# motor_driver_ver3_8.net
KiCad netlist of a schematic drawn in EAGLE
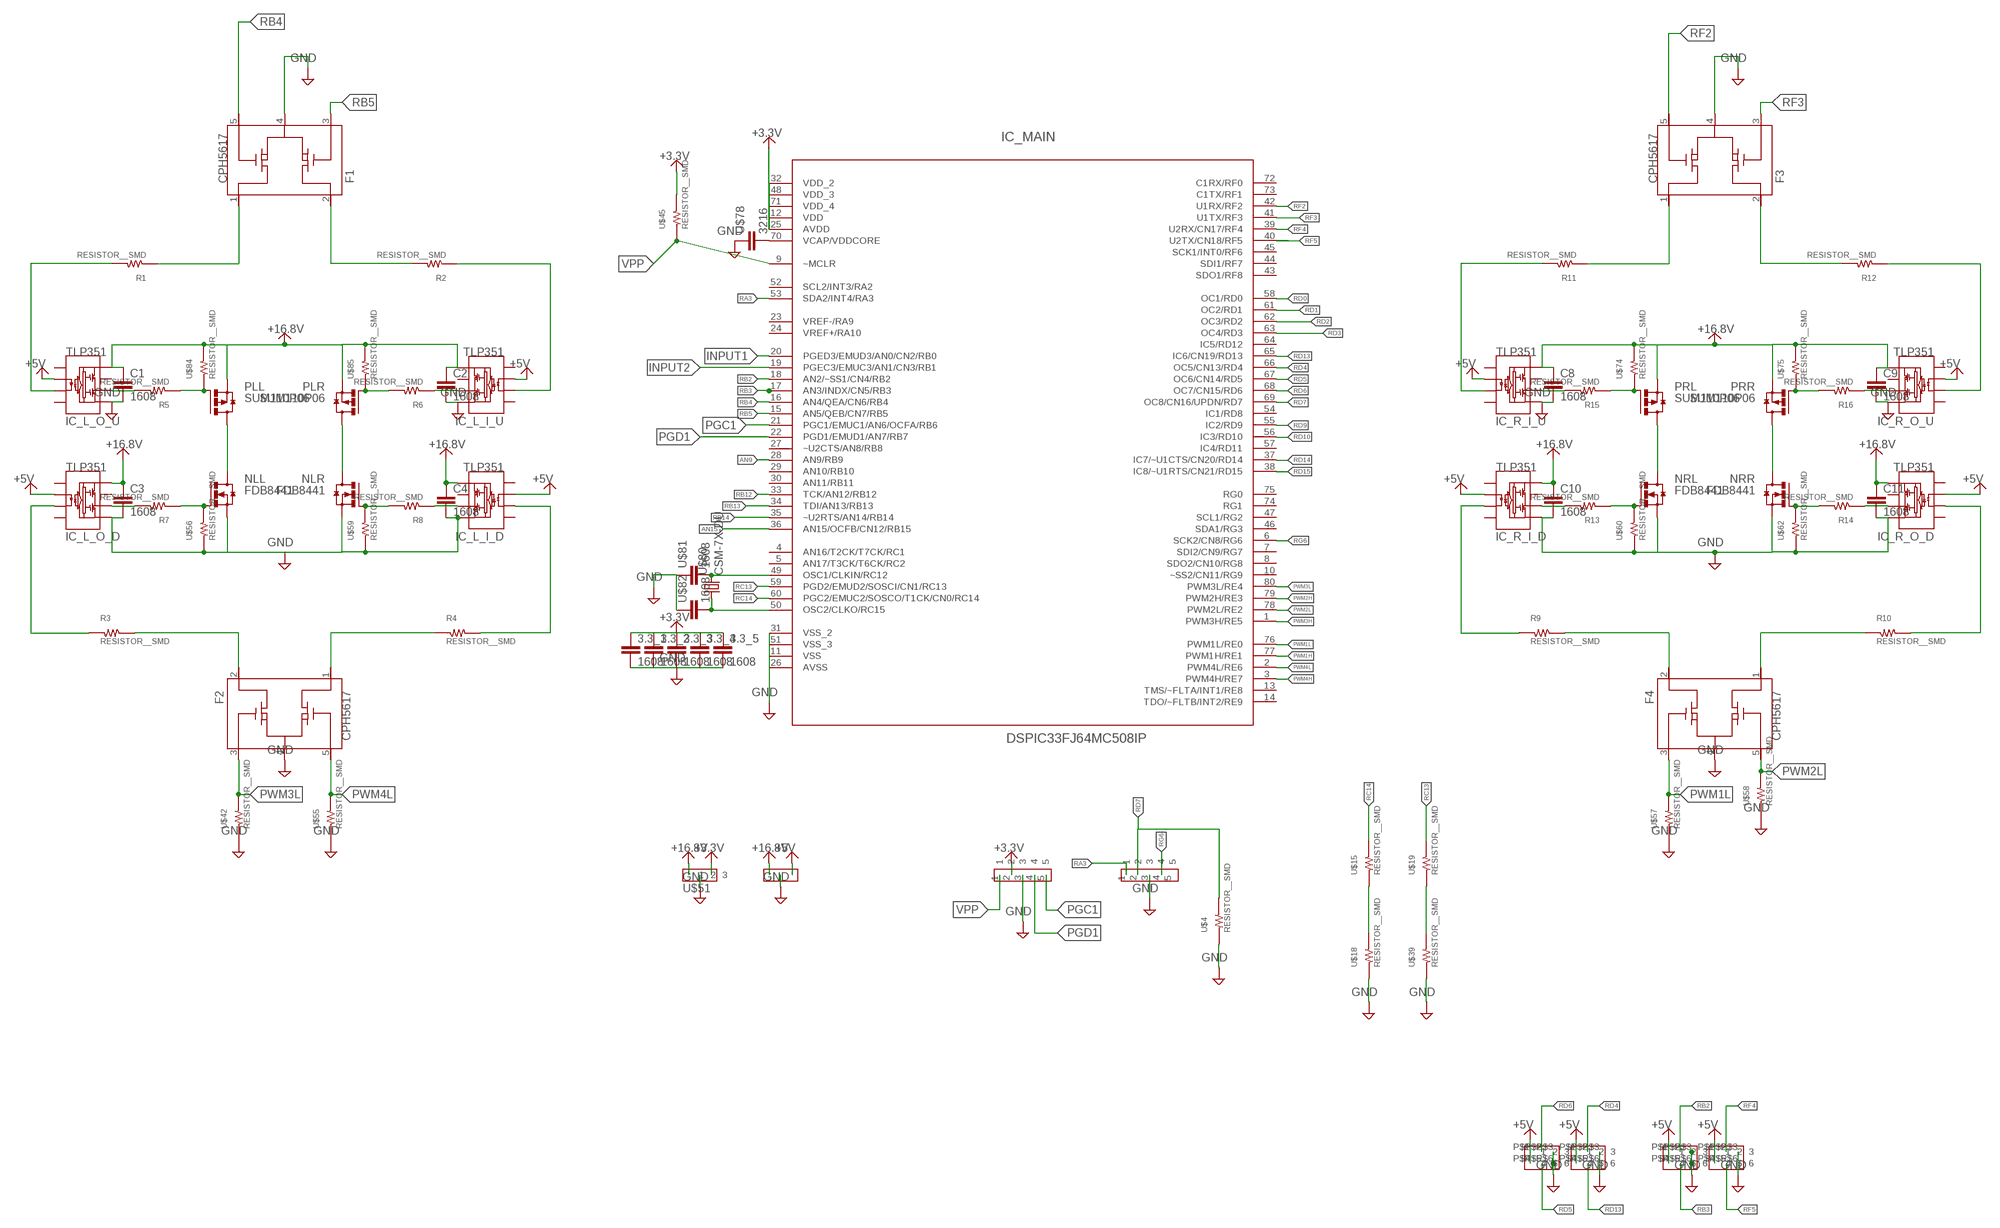
[diagram p0: schematic, sheet 1]

(export (version "E")
  (design (tool "Eeschema 10.0.6"))
  (components
    (comp (ref "3.3_1")
      (value "1608")
      (footprint "eagle-import:1608")
      (libsource (lib "eagle-import") (part "1608"))
    )
    (comp (ref "3.3_2")
      (value "1608")
      (footprint "eagle-import:1608")
      (libsource (lib "eagle-import") (part "1608"))
    )
    (comp (ref "3.3_3")
      (value "1608")
      (footprint "eagle-import:1608")
      (libsource (lib "eagle-import") (part "1608"))
    )
    (comp (ref "3.3_4")
      (value "1608")
      (footprint "eagle-import:1608")
      (libsource (lib "eagle-import") (part "1608"))
    )
    (comp (ref "3.3_5")
      (value "1608")
      (footprint "eagle-import:1608")
      (libsource (lib "eagle-import") (part "1608"))
    )
    (comp (ref "C1")
      (value "1608")
      (footprint "eagle-import:1608")
      (libsource (lib "eagle-import") (part "1608"))
    )
    (comp (ref "C2")
      (value "1608")
      (footprint "eagle-import:1608")
      (libsource (lib "eagle-import") (part "1608"))
    )
    (comp (ref "C3")
      (value "1608")
      (footprint "eagle-import:1608")
      (libsource (lib "eagle-import") (part "1608"))
    )
    (comp (ref "C4")
      (value "1608")
      (footprint "eagle-import:1608")
      (libsource (lib "eagle-import") (part "1608"))
    )
    (comp (ref "C8")
      (value "1608")
      (footprint "eagle-import:1608")
      (libsource (lib "eagle-import") (part "1608"))
    )
    (comp (ref "C9")
      (value "1608")
      (footprint "eagle-import:1608")
      (libsource (lib "eagle-import") (part "1608"))
    )
    (comp (ref "C10")
      (value "1608")
      (footprint "eagle-import:1608")
      (libsource (lib "eagle-import") (part "1608"))
    )
    (comp (ref "C11")
      (value "1608")
      (footprint "eagle-import:1608")
      (libsource (lib "eagle-import") (part "1608"))
    )
    (comp (ref "F1")
      (value "CPH5617")
      (footprint "eagle-import:CHP-5")
      (libsource (lib "eagle-import") (part "CPH5617"))
    )
    (comp (ref "F2")
      (value "CPH5617")
      (footprint "eagle-import:CHP-5")
      (libsource (lib "eagle-import") (part "CPH5617"))
    )
    (comp (ref "F3")
      (value "CPH5617")
      (footprint "eagle-import:CHP-5")
      (libsource (lib "eagle-import") (part "CPH5617"))
    )
    (comp (ref "F4")
      (value "CPH5617")
      (footprint "eagle-import:CHP-5")
      (libsource (lib "eagle-import") (part "CPH5617"))
    )
    (comp (ref "IC_L_I_D")
      (value "TLP351")
      (footprint "eagle-import:DIL08")
      (libsource (lib "eagle-import") (part "TLP351"))
    )
    (comp (ref "IC_L_I_U")
      (value "TLP351")
      (footprint "eagle-import:DIL08")
      (libsource (lib "eagle-import") (part "TLP351"))
    )
    (comp (ref "IC_L_O_D")
      (value "TLP351")
      (footprint "eagle-import:DIL08")
      (libsource (lib "eagle-import") (part "TLP351"))
    )
    (comp (ref "IC_L_O_U")
      (value "TLP351")
      (footprint "eagle-import:DIL08")
      (libsource (lib "eagle-import") (part "TLP351"))
    )
    (comp (ref "IC_MAIN")
      (value "DSPIC33FJ64MC508IP")
      (footprint "eagle-import:QFP50P1400X1400X120-80N")
      (libsource (lib "eagle-import") (part "DSPIC33FJ64MC508IP"))
    )
    (comp (ref "IC_R_I_D")
      (value "TLP351")
      (footprint "eagle-import:DIL08")
      (libsource (lib "eagle-import") (part "TLP351"))
    )
    (comp (ref "IC_R_I_U")
      (value "TLP351")
      (footprint "eagle-import:DIL08")
      (libsource (lib "eagle-import") (part "TLP351"))
    )
    (comp (ref "IC_R_O_D")
      (value "TLP351")
      (footprint "eagle-import:DIL08")
      (libsource (lib "eagle-import") (part "TLP351"))
    )
    (comp (ref "IC_R_O_U")
      (value "TLP351")
      (footprint "eagle-import:DIL08")
      (libsource (lib "eagle-import") (part "TLP351"))
    )
    (comp (ref "NLL")
      (value "FDB8441")
      (footprint "eagle-import:TO-263")
      (libsource (lib "eagle-import") (part "FDB8441"))
    )
    (comp (ref "NLR")
      (value "FDB8441")
      (footprint "eagle-import:TO-263")
      (libsource (lib "eagle-import") (part "FDB8441"))
    )
    (comp (ref "NRL")
      (value "FDB8441")
      (footprint "eagle-import:TO-263")
      (libsource (lib "eagle-import") (part "FDB8441"))
    )
    (comp (ref "NRR")
      (value "FDB8441")
      (footprint "eagle-import:TO-263")
      (libsource (lib "eagle-import") (part "FDB8441"))
    )
    (comp (ref "PLL")
      (value "SUM110P06")
      (footprint "eagle-import:TO-263")
      (libsource (lib "eagle-import") (part "SUM110P06"))
    )
    (comp (ref "PLR")
      (value "SUM110P06")
      (footprint "eagle-import:TO-263")
      (libsource (lib "eagle-import") (part "SUM110P06"))
    )
    (comp (ref "PRL")
      (value "SUM110P06")
      (footprint "eagle-import:TO-263")
      (libsource (lib "eagle-import") (part "SUM110P06"))
    )
    (comp (ref "PRR")
      (value "SUM110P06")
      (footprint "eagle-import:TO-263")
      (libsource (lib "eagle-import") (part "SUM110P06"))
    )
    (comp (ref "R1")
      (value "RESISTOR__SMD")
      (footprint "eagle-import:1608")
      (libsource (lib "eagle-import") (part "RESISTOR__SMD"))
    )
    (comp (ref "R2")
      (value "RESISTOR__SMD")
      (footprint "eagle-import:1608")
      (libsource (lib "eagle-import") (part "RESISTOR__SMD"))
    )
    (comp (ref "R3")
      (value "RESISTOR__SMD")
      (footprint "eagle-import:1608")
      (libsource (lib "eagle-import") (part "RESISTOR__SMD"))
    )
    (comp (ref "R4")
      (value "RESISTOR__SMD")
      (footprint "eagle-import:1608")
      (libsource (lib "eagle-import") (part "RESISTOR__SMD"))
    )
    (comp (ref "R5")
      (value "RESISTOR__SMD")
      (footprint "eagle-import:1608")
      (libsource (lib "eagle-import") (part "RESISTOR__SMD"))
    )
    (comp (ref "R6")
      (value "RESISTOR__SMD")
      (footprint "eagle-import:1608")
      (libsource (lib "eagle-import") (part "RESISTOR__SMD"))
    )
    (comp (ref "R7")
      (value "RESISTOR__SMD")
      (footprint "eagle-import:1608")
      (libsource (lib "eagle-import") (part "RESISTOR__SMD"))
    )
    (comp (ref "R8")
      (value "RESISTOR__SMD")
      (footprint "eagle-import:1608")
      (libsource (lib "eagle-import") (part "RESISTOR__SMD"))
    )
    (comp (ref "R9")
      (value "RESISTOR__SMD")
      (footprint "eagle-import:1608")
      (libsource (lib "eagle-import") (part "RESISTOR__SMD"))
    )
    (comp (ref "R10")
      (value "RESISTOR__SMD")
      (footprint "eagle-import:1608")
      (libsource (lib "eagle-import") (part "RESISTOR__SMD"))
    )
    (comp (ref "R11")
      (value "RESISTOR__SMD")
      (footprint "eagle-import:1608")
      (libsource (lib "eagle-import") (part "RESISTOR__SMD"))
    )
    (comp (ref "R12")
      (value "RESISTOR__SMD")
      (footprint "eagle-import:1608")
      (libsource (lib "eagle-import") (part "RESISTOR__SMD"))
    )
    (comp (ref "R13")
      (value "RESISTOR__SMD")
      (footprint "eagle-import:1608")
      (libsource (lib "eagle-import") (part "RESISTOR__SMD"))
    )
    (comp (ref "R14")
      (value "RESISTOR__SMD")
      (footprint "eagle-import:1608")
      (libsource (lib "eagle-import") (part "RESISTOR__SMD"))
    )
    (comp (ref "R15")
      (value "RESISTOR__SMD")
      (footprint "eagle-import:1608")
      (libsource (lib "eagle-import") (part "RESISTOR__SMD"))
    )
    (comp (ref "R16")
      (value "RESISTOR__SMD")
      (footprint "eagle-import:1608")
      (libsource (lib "eagle-import") (part "RESISTOR__SMD"))
    )
    (comp (ref "U$1")
      (value "PIN_HEADER_5")
      (footprint "eagle-import:PIN_HEADER_5")
      (libsource (lib "eagle-import") (part "PIN_HEADER_5"))
    )
    (comp (ref "U$4")
      (value "RESISTOR__SMD")
      (footprint "eagle-import:1608")
      (libsource (lib "eagle-import") (part "RESISTOR__SMD"))
    )
    (comp (ref "U$5")
      (value "PIN_HEADER_32")
      (footprint "eagle-import:PIN_HEADER_3_2")
      (libsource (lib "eagle-import") (part "PIN_HEADER_32"))
    )
    (comp (ref "U$15")
      (value "RESISTOR__SMD")
      (footprint "eagle-import:1608")
      (libsource (lib "eagle-import") (part "RESISTOR__SMD"))
    )
    (comp (ref "U$18")
      (value "RESISTOR__SMD")
      (footprint "eagle-import:1608")
      (libsource (lib "eagle-import") (part "RESISTOR__SMD"))
    )
    (comp (ref "U$19")
      (value "RESISTOR__SMD")
      (footprint "eagle-import:1608")
      (libsource (lib "eagle-import") (part "RESISTOR__SMD"))
    )
    (comp (ref "U$20")
      (value "PIN_HEADER_32")
      (footprint "eagle-import:PIN_HEADER_3_2")
      (libsource (lib "eagle-import") (part "PIN_HEADER_32"))
    )
    (comp (ref "U$39")
      (value "RESISTOR__SMD")
      (footprint "eagle-import:1608")
      (libsource (lib "eagle-import") (part "RESISTOR__SMD"))
    )
    (comp (ref "U$42")
      (value "RESISTOR__SMD")
      (footprint "eagle-import:1608")
      (libsource (lib "eagle-import") (part "RESISTOR__SMD"))
    )
    (comp (ref "U$45")
      (value "RESISTOR__SMD")
      (footprint "eagle-import:1608")
      (libsource (lib "eagle-import") (part "RESISTOR__SMD"))
    )
    (comp (ref "U$47")
      (value "TA48M05")
      (footprint "eagle-import:ＨＳＩＰ３")
      (libsource (lib "eagle-import") (part "TA48M05"))
    )
    (comp (ref "U$51")
      (value "TA48M033")
      (footprint "eagle-import:ＨＳＩＰ３")
      (libsource (lib "eagle-import") (part "TA48M033"))
    )
    (comp (ref "U$55")
      (value "RESISTOR__SMD")
      (footprint "eagle-import:1608")
      (libsource (lib "eagle-import") (part "RESISTOR__SMD"))
    )
    (comp (ref "U$56")
      (value "RESISTOR__SMD")
      (footprint "eagle-import:1608")
      (libsource (lib "eagle-import") (part "RESISTOR__SMD"))
    )
    (comp (ref "U$57")
      (value "RESISTOR__SMD")
      (footprint "eagle-import:1608")
      (libsource (lib "eagle-import") (part "RESISTOR__SMD"))
    )
    (comp (ref "U$58")
      (value "RESISTOR__SMD")
      (footprint "eagle-import:1608")
      (libsource (lib "eagle-import") (part "RESISTOR__SMD"))
    )
    (comp (ref "U$59")
      (value "RESISTOR__SMD")
      (footprint "eagle-import:1608")
      (libsource (lib "eagle-import") (part "RESISTOR__SMD"))
    )
    (comp (ref "U$60")
      (value "RESISTOR__SMD")
      (footprint "eagle-import:1608")
      (libsource (lib "eagle-import") (part "RESISTOR__SMD"))
    )
    (comp (ref "U$62")
      (value "RESISTOR__SMD")
      (footprint "eagle-import:1608")
      (libsource (lib "eagle-import") (part "RESISTOR__SMD"))
    )
    (comp (ref "U$64")
      (value "PIN_HEADER_5")
      (footprint "eagle-import:PIN_HEADER_5")
      (libsource (lib "eagle-import") (part "PIN_HEADER_5"))
    )
    (comp (ref "U$66")
      (value "PIN_HEADER_32")
      (footprint "eagle-import:PIN_HEADER_3_2")
      (libsource (lib "eagle-import") (part "PIN_HEADER_32"))
    )
    (comp (ref "U$67")
      (value "PIN_HEADER_32")
      (footprint "eagle-import:PIN_HEADER_3_2")
      (libsource (lib "eagle-import") (part "PIN_HEADER_32"))
    )
    (comp (ref "U$74")
      (value "RESISTOR__SMD")
      (footprint "eagle-import:1608")
      (libsource (lib "eagle-import") (part "RESISTOR__SMD"))
    )
    (comp (ref "U$75")
      (value "RESISTOR__SMD")
      (footprint "eagle-import:1608")
      (libsource (lib "eagle-import") (part "RESISTOR__SMD"))
    )
    (comp (ref "U$78")
      (value "3216")
      (footprint "eagle-import:3216")
      (libsource (lib "eagle-import") (part "3216"))
    )
    (comp (ref "U$80")
      (value "CSM-7X-DU")
      (footprint "eagle-import:CSM-7X-DU")
      (libsource (lib "eagle-import") (part "CSM-7X-DU"))
    )
    (comp (ref "U$81")
      (value "1608")
      (footprint "eagle-import:1608")
      (libsource (lib "eagle-import") (part "1608"))
    )
    (comp (ref "U$82")
      (value "1608")
      (footprint "eagle-import:1608")
      (libsource (lib "eagle-import") (part "1608"))
    )
    (comp (ref "U$84")
      (value "RESISTOR__SMD")
      (footprint "eagle-import:1608")
      (libsource (lib "eagle-import") (part "RESISTOR__SMD"))
    )
    (comp (ref "U$85")
      (value "RESISTOR__SMD")
      (footprint "eagle-import:1608")
      (libsource (lib "eagle-import") (part "RESISTOR__SMD"))
    )
  )
  (nets
    (net (code "1") (name "+3.3V") (class "Default")
      (node (ref "3.3_1") (pin "P$1") (pinfunction "1_P$1") (pintype "passive"))
      (node (ref "3.3_2") (pin "P$1") (pinfunction "1_P$1") (pintype "passive"))
      (node (ref "3.3_3") (pin "P$1") (pinfunction "1_P$1") (pintype "passive"))
      (node (ref "3.3_4") (pin "P$1") (pinfunction "1_P$1") (pintype "passive"))
      (node (ref "3.3_5") (pin "P$1") (pinfunction "1_P$1") (pintype "passive"))
      (node (ref "IC_MAIN") (pin "12") (pinfunction "VDD_12") (pintype "power_in"))
      (node (ref "IC_MAIN") (pin "25") (pinfunction "AVDD_25") (pintype "power_in"))
      (node (ref "IC_MAIN") (pin "32") (pinfunction "VDD_2_32") (pintype "power_in"))
      (node (ref "IC_MAIN") (pin "48") (pinfunction "VDD_3_48") (pintype "power_in"))
      (node (ref "IC_MAIN") (pin "71") (pinfunction "VDD_4_71") (pintype "power_in"))
      (node (ref "U$1") (pin "2") (pinfunction "2_2") (pintype "bidirectional"))
      (node (ref "U$45") (pin "2") (pinfunction "P$2_2") (pintype "passive"))
      (node (ref "U$51") (pin "3") (pinfunction "3_3") (pintype "bidirectional"))
    )
    (net (code "2") (name "+5V") (class "Default")
      (node (ref "IC_L_I_D") (pin "2") (pinfunction "LED+_2") (pintype "bidirectional"))
      (node (ref "IC_L_I_U") (pin "2") (pinfunction "LED+_2") (pintype "bidirectional"))
      (node (ref "IC_L_O_D") (pin "2") (pinfunction "LED+_2") (pintype "bidirectional"))
      (node (ref "IC_L_O_U") (pin "2") (pinfunction "LED+_2") (pintype "bidirectional"))
      (node (ref "IC_R_I_D") (pin "2") (pinfunction "LED+_2") (pintype "bidirectional"))
      (node (ref "IC_R_I_U") (pin "2") (pinfunction "LED+_2") (pintype "bidirectional"))
      (node (ref "IC_R_O_D") (pin "2") (pinfunction "LED+_2") (pintype "bidirectional"))
      (node (ref "IC_R_O_U") (pin "2") (pinfunction "LED+_2") (pintype "bidirectional"))
      (node (ref "U$20") (pin "P$1") (pinfunction "1_P$1") (pintype "bidirectional"))
      (node (ref "U$20") (pin "P$4") (pinfunction "4_P$4") (pintype "bidirectional"))
      (node (ref "U$47") (pin "3") (pinfunction "OUT_3") (pintype "bidirectional"))
      (node (ref "U$5") (pin "P$1") (pinfunction "1_P$1") (pintype "bidirectional"))
      (node (ref "U$5") (pin "P$4") (pinfunction "4_P$4") (pintype "bidirectional"))
      (node (ref "U$66") (pin "P$1") (pinfunction "1_P$1") (pintype "bidirectional"))
      (node (ref "U$66") (pin "P$4") (pinfunction "4_P$4") (pintype "bidirectional"))
      (node (ref "U$67") (pin "P$1") (pinfunction "1_P$1") (pintype "bidirectional"))
      (node (ref "U$67") (pin "P$4") (pinfunction "4_P$4") (pintype "bidirectional"))
    )
    (net (code "3") (name "+16.8V") (class "Default")
      (node (ref "C1") (pin "P$1") (pinfunction "1_P$1") (pintype "passive"))
      (node (ref "C10") (pin "P$1") (pinfunction "1_P$1") (pintype "passive"))
      (node (ref "C11") (pin "P$1") (pinfunction "1_P$1") (pintype "passive"))
      (node (ref "C2") (pin "P$1") (pinfunction "1_P$1") (pintype "passive"))
      (node (ref "C3") (pin "P$1") (pinfunction "1_P$1") (pintype "passive"))
      (node (ref "C4") (pin "P$1") (pinfunction "1_P$1") (pintype "passive"))
      (node (ref "C8") (pin "P$1") (pinfunction "1_P$1") (pintype "passive"))
      (node (ref "C9") (pin "P$1") (pinfunction "1_P$1") (pintype "passive"))
      (node (ref "IC_L_I_D") (pin "8") (pinfunction "VDD_8") (pintype "bidirectional"))
      (node (ref "IC_L_I_U") (pin "8") (pinfunction "VDD_8") (pintype "bidirectional"))
      (node (ref "IC_L_O_D") (pin "8") (pinfunction "VDD_8") (pintype "bidirectional"))
      (node (ref "IC_L_O_U") (pin "8") (pinfunction "VDD_8") (pintype "bidirectional"))
      (node (ref "IC_R_I_D") (pin "8") (pinfunction "VDD_8") (pintype "bidirectional"))
      (node (ref "IC_R_I_U") (pin "8") (pinfunction "VDD_8") (pintype "bidirectional"))
      (node (ref "IC_R_O_D") (pin "8") (pinfunction "VDD_8") (pintype "bidirectional"))
      (node (ref "IC_R_O_U") (pin "8") (pinfunction "VDD_8") (pintype "bidirectional"))
      (node (ref "PLL") (pin "2") (pinfunction "S_2") (pintype "passive"))
      (node (ref "PLR") (pin "2") (pinfunction "S_2") (pintype "passive"))
      (node (ref "PRL") (pin "2") (pinfunction "S_2") (pintype "passive"))
      (node (ref "PRR") (pin "2") (pinfunction "S_2") (pintype "passive"))
      (node (ref "U$47") (pin "1") (pinfunction "IN_1") (pintype "bidirectional"))
      (node (ref "U$51") (pin "1") (pinfunction "1_1") (pintype "bidirectional"))
      (node (ref "U$74") (pin "2") (pinfunction "P$2_2") (pintype "passive"))
      (node (ref "U$75") (pin "2") (pinfunction "P$2_2") (pintype "passive"))
      (node (ref "U$84") (pin "2") (pinfunction "P$2_2") (pintype "passive"))
      (node (ref "U$85") (pin "2") (pinfunction "P$2_2") (pintype "passive"))
    )
    (net (code "4") (name "AN9") (class "Default")
      (node (ref "IC_MAIN") (pin "28") (pinfunction "AN9/RB9_28") (pintype "bidirectional"))
    )
    (net (code "5") (name "AN15") (class "Default")
      (node (ref "IC_MAIN") (pin "36") (pinfunction "AN15/OCFB/CN12/RB15_36") (pintype "bidirectional"))
    )
    (net (code "6") (name "GND") (class "Default")
      (node (ref "3.3_1") (pin "P$2") (pinfunction "2_P$2") (pintype "passive"))
      (node (ref "3.3_2") (pin "P$2") (pinfunction "2_P$2") (pintype "passive"))
      (node (ref "3.3_3") (pin "P$2") (pinfunction "2_P$2") (pintype "passive"))
      (node (ref "3.3_4") (pin "P$2") (pinfunction "2_P$2") (pintype "passive"))
      (node (ref "3.3_5") (pin "P$2") (pinfunction "2_P$2") (pintype "passive"))
      (node (ref "C1") (pin "P$2") (pinfunction "2_P$2") (pintype "passive"))
      (node (ref "C10") (pin "P$2") (pinfunction "2_P$2") (pintype "passive"))
      (node (ref "C11") (pin "P$2") (pinfunction "2_P$2") (pintype "passive"))
      (node (ref "C2") (pin "P$2") (pinfunction "2_P$2") (pintype "passive"))
      (node (ref "C3") (pin "P$2") (pinfunction "2_P$2") (pintype "passive"))
      (node (ref "C4") (pin "P$2") (pinfunction "2_P$2") (pintype "passive"))
      (node (ref "C8") (pin "P$2") (pinfunction "2_P$2") (pintype "passive"))
      (node (ref "C9") (pin "P$2") (pinfunction "2_P$2") (pintype "passive"))
      (node (ref "F1") (pin "4") (pinfunction "S_4") (pintype "bidirectional"))
      (node (ref "F2") (pin "4") (pinfunction "S_4") (pintype "bidirectional"))
      (node (ref "F3") (pin "4") (pinfunction "S_4") (pintype "bidirectional"))
      (node (ref "F4") (pin "4") (pinfunction "S_4") (pintype "bidirectional"))
      (node (ref "IC_L_I_D") (pin "5") (pinfunction "GND_5") (pintype "bidirectional"))
      (node (ref "IC_L_I_U") (pin "5") (pinfunction "GND_5") (pintype "bidirectional"))
      (node (ref "IC_L_O_D") (pin "5") (pinfunction "GND_5") (pintype "bidirectional"))
      (node (ref "IC_L_O_U") (pin "5") (pinfunction "GND_5") (pintype "bidirectional"))
      (node (ref "IC_MAIN") (pin "11") (pinfunction "VSS_11") (pintype "power_in"))
      (node (ref "IC_MAIN") (pin "26") (pinfunction "AVSS_26") (pintype "power_in"))
      (node (ref "IC_MAIN") (pin "31") (pinfunction "VSS_2_31") (pintype "power_in"))
      (node (ref "IC_MAIN") (pin "51") (pinfunction "VSS_3_51") (pintype "power_in"))
      (node (ref "IC_R_I_D") (pin "5") (pinfunction "GND_5") (pintype "bidirectional"))
      (node (ref "IC_R_I_U") (pin "5") (pinfunction "GND_5") (pintype "bidirectional"))
      (node (ref "IC_R_O_D") (pin "5") (pinfunction "GND_5") (pintype "bidirectional"))
      (node (ref "IC_R_O_U") (pin "5") (pinfunction "GND_5") (pintype "bidirectional"))
      (node (ref "NLL") (pin "2") (pinfunction "S_2") (pintype "passive"))
      (node (ref "NLR") (pin "2") (pinfunction "S_2") (pintype "passive"))
      (node (ref "NRL") (pin "2") (pinfunction "S_2") (pintype "passive"))
      (node (ref "NRR") (pin "2") (pinfunction "S_2") (pintype "passive"))
      (node (ref "U$1") (pin "3") (pinfunction "3_3") (pintype "bidirectional"))
      (node (ref "U$18") (pin "1") (pinfunction "P$1_1") (pintype "passive"))
      (node (ref "U$20") (pin "P$3") (pinfunction "3_P$3") (pintype "bidirectional"))
      (node (ref "U$20") (pin "P$6") (pinfunction "6_P$6") (pintype "bidirectional"))
      (node (ref "U$39") (pin "1") (pinfunction "P$1_1") (pintype "passive"))
      (node (ref "U$4") (pin "1") (pinfunction "P$1_1") (pintype "passive"))
      (node (ref "U$42") (pin "1") (pinfunction "P$1_1") (pintype "passive"))
      (node (ref "U$47") (pin "2") (pinfunction "GND_2") (pintype "bidirectional"))
      (node (ref "U$5") (pin "P$3") (pinfunction "3_P$3") (pintype "bidirectional"))
      (node (ref "U$5") (pin "P$6") (pinfunction "6_P$6") (pintype "bidirectional"))
      (node (ref "U$51") (pin "2") (pinfunction "2_2") (pintype "bidirectional"))
      (node (ref "U$55") (pin "1") (pinfunction "P$1_1") (pintype "passive"))
      (node (ref "U$56") (pin "1") (pinfunction "P$1_1") (pintype "passive"))
      (node (ref "U$57") (pin "1") (pinfunction "P$1_1") (pintype "passive"))
      (node (ref "U$58") (pin "1") (pinfunction "P$1_1") (pintype "passive"))
      (node (ref "U$59") (pin "1") (pinfunction "P$1_1") (pintype "passive"))
      (node (ref "U$60") (pin "1") (pinfunction "P$1_1") (pintype "passive"))
      (node (ref "U$62") (pin "1") (pinfunction "P$1_1") (pintype "passive"))
      (node (ref "U$64") (pin "3") (pinfunction "3_3") (pintype "bidirectional"))
      (node (ref "U$66") (pin "P$3") (pinfunction "3_P$3") (pintype "bidirectional"))
      (node (ref "U$66") (pin "P$6") (pinfunction "6_P$6") (pintype "bidirectional"))
      (node (ref "U$67") (pin "P$3") (pinfunction "3_P$3") (pintype "bidirectional"))
      (node (ref "U$67") (pin "P$6") (pinfunction "6_P$6") (pintype "bidirectional"))
      (node (ref "U$78") (pin "P$1") (pinfunction "1_P$1") (pintype "passive"))
      (node (ref "U$81") (pin "P$1") (pinfunction "1_P$1") (pintype "passive"))
      (node (ref "U$82") (pin "P$1") (pinfunction "1_P$1") (pintype "passive"))
    )
    (net (code "7") (name "INPUT1") (class "Default")
      (node (ref "IC_MAIN") (pin "20") (pinfunction "PGED3/EMUD3/AN0/CN2/RB0_20") (pintype "bidirectional"))
    )
    (net (code "8") (name "INPUT2") (class "Default")
      (node (ref "IC_MAIN") (pin "19") (pinfunction "PGEC3/EMUC3/AN1/CN3/RB1_19") (pintype "bidirectional"))
    )
    (net (code "9") (name "Net-(F1-D1)") (class "Default")
      (node (ref "F1") (pin "1") (pinfunction "D1_1") (pintype "bidirectional"))
      (node (ref "R1") (pin "1") (pinfunction "P$1_1") (pintype "passive"))
    )
    (net (code "10") (name "Net-(F1-D2)") (class "Default")
      (node (ref "F1") (pin "2") (pinfunction "D2_2") (pintype "bidirectional"))
      (node (ref "R2") (pin "2") (pinfunction "P$2_2") (pintype "passive"))
    )
    (net (code "11") (name "Net-(F2-D1)") (class "Default")
      (node (ref "F2") (pin "1") (pinfunction "D1_1") (pintype "bidirectional"))
      (node (ref "R4") (pin "1") (pinfunction "P$1_1") (pintype "passive"))
    )
    (net (code "12") (name "Net-(F2-D2)") (class "Default")
      (node (ref "F2") (pin "2") (pinfunction "D2_2") (pintype "bidirectional"))
      (node (ref "R3") (pin "2") (pinfunction "P$2_2") (pintype "passive"))
    )
    (net (code "13") (name "Net-(F3-D1)") (class "Default")
      (node (ref "F3") (pin "1") (pinfunction "D1_1") (pintype "bidirectional"))
      (node (ref "R11") (pin "1") (pinfunction "P$1_1") (pintype "passive"))
    )
    (net (code "14") (name "Net-(F3-D2)") (class "Default")
      (node (ref "F3") (pin "2") (pinfunction "D2_2") (pintype "bidirectional"))
      (node (ref "R12") (pin "2") (pinfunction "P$2_2") (pintype "passive"))
    )
    (net (code "15") (name "Net-(F4-D1)") (class "Default")
      (node (ref "F4") (pin "1") (pinfunction "D1_1") (pintype "bidirectional"))
      (node (ref "R10") (pin "1") (pinfunction "P$1_1") (pintype "passive"))
    )
    (net (code "16") (name "Net-(F4-D2)") (class "Default")
      (node (ref "F4") (pin "2") (pinfunction "D2_2") (pintype "bidirectional"))
      (node (ref "R9") (pin "2") (pinfunction "P$2_2") (pintype "passive"))
    )
    (net (code "17") (name "Net-(IC_L_I_D-LED-)") (class "Default")
      (node (ref "IC_L_I_D") (pin "3") (pinfunction "LED-_3") (pintype "bidirectional"))
      (node (ref "R4") (pin "2") (pinfunction "P$2_2") (pintype "passive"))
    )
    (net (code "18") (name "Net-(IC_L_I_D-OUT)") (class "Default")
      (node (ref "IC_L_I_D") (pin "6") (pinfunction "OUT_6") (pintype "output"))
      (node (ref "R8") (pin "1") (pinfunction "P$1_1") (pintype "passive"))
    )
    (net (code "19") (name "Net-(IC_L_I_U-LED-)") (class "Default")
      (node (ref "IC_L_I_U") (pin "3") (pinfunction "LED-_3") (pintype "bidirectional"))
      (node (ref "R2") (pin "1") (pinfunction "P$1_1") (pintype "passive"))
    )
    (net (code "20") (name "Net-(IC_L_I_U-OUT)") (class "Default")
      (node (ref "IC_L_I_U") (pin "6") (pinfunction "OUT_6") (pintype "output"))
      (node (ref "R6") (pin "1") (pinfunction "P$1_1") (pintype "passive"))
    )
    (net (code "21") (name "Net-(IC_L_O_D-LED-)") (class "Default")
      (node (ref "IC_L_O_D") (pin "3") (pinfunction "LED-_3") (pintype "bidirectional"))
      (node (ref "R3") (pin "1") (pinfunction "P$1_1") (pintype "passive"))
    )
    (net (code "22") (name "Net-(IC_L_O_D-OUT)") (class "Default")
      (node (ref "IC_L_O_D") (pin "6") (pinfunction "OUT_6") (pintype "output"))
      (node (ref "R7") (pin "2") (pinfunction "P$2_2") (pintype "passive"))
    )
    (net (code "23") (name "Net-(IC_L_O_U-LED-)") (class "Default")
      (node (ref "IC_L_O_U") (pin "3") (pinfunction "LED-_3") (pintype "bidirectional"))
      (node (ref "R1") (pin "2") (pinfunction "P$2_2") (pintype "passive"))
    )
    (net (code "24") (name "Net-(IC_L_O_U-OUT)") (class "Default")
      (node (ref "IC_L_O_U") (pin "6") (pinfunction "OUT_6") (pintype "output"))
      (node (ref "R5") (pin "2") (pinfunction "P$2_2") (pintype "passive"))
    )
    (net (code "25") (name "Net-(IC_MAIN-OSC1{slash}CLKIN{slash}RC12)") (class "Default")
      (node (ref "IC_MAIN") (pin "49") (pinfunction "OSC1/CLKIN/RC12_49") (pintype "bidirectional"))
      (node (ref "U$80") (pin "2") (pinfunction "2_2") (pintype "passive"))
      (node (ref "U$81") (pin "P$2") (pinfunction "2_P$2") (pintype "passive"))
    )
    (net (code "26") (name "Net-(IC_MAIN-OSC2{slash}CLKO{slash}RC15)") (class "Default")
      (node (ref "IC_MAIN") (pin "50") (pinfunction "OSC2/CLKO/RC15_50") (pintype "bidirectional"))
      (node (ref "U$80") (pin "1") (pinfunction "1_1") (pintype "passive"))
      (node (ref "U$82") (pin "P$2") (pinfunction "2_P$2") (pintype "passive"))
    )
    (net (code "27") (name "Net-(IC_MAIN-VCAP{slash}VDDCORE)") (class "Default")
      (node (ref "IC_MAIN") (pin "70") (pinfunction "VCAP/VDDCORE_70") (pintype "power_in"))
      (node (ref "U$78") (pin "P$2") (pinfunction "2_P$2") (pintype "passive"))
    )
    (net (code "28") (name "Net-(IC_R_I_D-LED-)") (class "Default")
      (node (ref "IC_R_I_D") (pin "3") (pinfunction "LED-_3") (pintype "bidirectional"))
      (node (ref "R9") (pin "1") (pinfunction "P$1_1") (pintype "passive"))
    )
    (net (code "29") (name "Net-(IC_R_I_D-OUT)") (class "Default")
      (node (ref "IC_R_I_D") (pin "6") (pinfunction "OUT_6") (pintype "output"))
      (node (ref "R13") (pin "2") (pinfunction "P$2_2") (pintype "passive"))
    )
    (net (code "30") (name "Net-(IC_R_I_U-LED-)") (class "Default")
      (node (ref "IC_R_I_U") (pin "3") (pinfunction "LED-_3") (pintype "bidirectional"))
      (node (ref "R11") (pin "2") (pinfunction "P$2_2") (pintype "passive"))
    )
    (net (code "31") (name "Net-(IC_R_I_U-OUT)") (class "Default")
      (node (ref "IC_R_I_U") (pin "6") (pinfunction "OUT_6") (pintype "output"))
      (node (ref "R15") (pin "2") (pinfunction "P$2_2") (pintype "passive"))
    )
    (net (code "32") (name "Net-(IC_R_O_D-LED-)") (class "Default")
      (node (ref "IC_R_O_D") (pin "3") (pinfunction "LED-_3") (pintype "bidirectional"))
      (node (ref "R10") (pin "2") (pinfunction "P$2_2") (pintype "passive"))
    )
    (net (code "33") (name "Net-(IC_R_O_D-OUT)") (class "Default")
      (node (ref "IC_R_O_D") (pin "6") (pinfunction "OUT_6") (pintype "output"))
      (node (ref "R14") (pin "1") (pinfunction "P$1_1") (pintype "passive"))
    )
    (net (code "34") (name "Net-(IC_R_O_U-LED-)") (class "Default")
      (node (ref "IC_R_O_U") (pin "3") (pinfunction "LED-_3") (pintype "bidirectional"))
      (node (ref "R12") (pin "1") (pinfunction "P$1_1") (pintype "passive"))
    )
    (net (code "35") (name "Net-(IC_R_O_U-OUT)") (class "Default")
      (node (ref "IC_R_O_U") (pin "6") (pinfunction "OUT_6") (pintype "output"))
      (node (ref "R16") (pin "1") (pinfunction "P$1_1") (pintype "passive"))
    )
    (net (code "36") (name "Net-(NLL-D)") (class "Default")
      (node (ref "NLL") (pin "3") (pinfunction "D_3") (pintype "passive"))
      (node (ref "PLL") (pin "3") (pinfunction "D_3") (pintype "passive"))
    )
    (net (code "37") (name "Net-(NLL-G)") (class "Default")
      (node (ref "NLL") (pin "1") (pinfunction "G_1") (pintype "passive"))
      (node (ref "R7") (pin "1") (pinfunction "P$1_1") (pintype "passive"))
      (node (ref "U$56") (pin "2") (pinfunction "P$2_2") (pintype "passive"))
    )
    (net (code "38") (name "Net-(NLR-D)") (class "Default")
      (node (ref "NLR") (pin "3") (pinfunction "D_3") (pintype "passive"))
      (node (ref "PLR") (pin "3") (pinfunction "D_3") (pintype "passive"))
    )
    (net (code "39") (name "Net-(NLR-G)") (class "Default")
      (node (ref "NLR") (pin "1") (pinfunction "G_1") (pintype "passive"))
      (node (ref "R8") (pin "2") (pinfunction "P$2_2") (pintype "passive"))
      (node (ref "U$59") (pin "2") (pinfunction "P$2_2") (pintype "passive"))
    )
    (net (code "40") (name "Net-(NRL-D)") (class "Default")
      (node (ref "NRL") (pin "3") (pinfunction "D_3") (pintype "passive"))
      (node (ref "PRL") (pin "3") (pinfunction "D_3") (pintype "passive"))
    )
    (net (code "41") (name "Net-(NRL-G)") (class "Default")
      (node (ref "NRL") (pin "1") (pinfunction "G_1") (pintype "passive"))
      (node (ref "R13") (pin "1") (pinfunction "P$1_1") (pintype "passive"))
      (node (ref "U$60") (pin "2") (pinfunction "P$2_2") (pintype "passive"))
    )
    (net (code "42") (name "Net-(NRR-D)") (class "Default")
      (node (ref "NRR") (pin "3") (pinfunction "D_3") (pintype "passive"))
      (node (ref "PRR") (pin "3") (pinfunction "D_3") (pintype "passive"))
    )
    (net (code "43") (name "Net-(NRR-G)") (class "Default")
      (node (ref "NRR") (pin "1") (pinfunction "G_1") (pintype "passive"))
      (node (ref "R14") (pin "2") (pinfunction "P$2_2") (pintype "passive"))
      (node (ref "U$62") (pin "2") (pinfunction "P$2_2") (pintype "passive"))
    )
    (net (code "44") (name "Net-(PLL-G)") (class "Default")
      (node (ref "PLL") (pin "1") (pinfunction "G_1") (pintype "passive"))
      (node (ref "R5") (pin "1") (pinfunction "P$1_1") (pintype "passive"))
      (node (ref "U$84") (pin "1") (pinfunction "P$1_1") (pintype "passive"))
    )
    (net (code "45") (name "Net-(PLR-G)") (class "Default")
      (node (ref "PLR") (pin "1") (pinfunction "G_1") (pintype "passive"))
      (node (ref "R6") (pin "2") (pinfunction "P$2_2") (pintype "passive"))
      (node (ref "U$85") (pin "1") (pinfunction "P$1_1") (pintype "passive"))
    )
    (net (code "46") (name "Net-(PRL-G)") (class "Default")
      (node (ref "PRL") (pin "1") (pinfunction "G_1") (pintype "passive"))
      (node (ref "R15") (pin "1") (pinfunction "P$1_1") (pintype "passive"))
      (node (ref "U$74") (pin "1") (pinfunction "P$1_1") (pintype "passive"))
    )
    (net (code "47") (name "Net-(PRR-G)") (class "Default")
      (node (ref "PRR") (pin "1") (pinfunction "G_1") (pintype "passive"))
      (node (ref "R16") (pin "2") (pinfunction "P$2_2") (pintype "passive"))
      (node (ref "U$75") (pin "1") (pinfunction "P$1_1") (pintype "passive"))
    )
    (net (code "48") (name "Net-(U$15-P$1)") (class "Default")
      (node (ref "U$15") (pin "1") (pinfunction "P$1_1") (pintype "passive"))
      (node (ref "U$18") (pin "2") (pinfunction "P$2_2") (pintype "passive"))
    )
    (net (code "49") (name "Net-(U$19-P$1)") (class "Default")
      (node (ref "U$19") (pin "1") (pinfunction "P$1_1") (pintype "passive"))
      (node (ref "U$39") (pin "2") (pinfunction "P$2_2") (pintype "passive"))
    )
    (net (code "50") (name "PGC1") (class "Default")
      (node (ref "IC_MAIN") (pin "21") (pinfunction "PGC1/EMUC1/AN6/OCFA/RB6_21") (pintype "bidirectional"))
      (node (ref "U$1") (pin "5") (pinfunction "5_5") (pintype "bidirectional"))
    )
    (net (code "51") (name "PGD1") (class "Default")
      (node (ref "IC_MAIN") (pin "22") (pinfunction "PGD1/EMUD1/AN7/RB7_22") (pintype "bidirectional"))
      (node (ref "U$1") (pin "4") (pinfunction "4_4") (pintype "bidirectional"))
    )
    (net (code "52") (name "PWM1H") (class "Default")
      (node (ref "IC_MAIN") (pin "77") (pinfunction "PWM1H/RE1_77") (pintype "bidirectional"))
    )
    (net (code "53") (name "PWM1L") (class "Default")
      (node (ref "F4") (pin "3") (pinfunction "G2_3") (pintype "bidirectional"))
      (node (ref "IC_MAIN") (pin "76") (pinfunction "PWM1L/RE0_76") (pintype "bidirectional"))
      (node (ref "U$57") (pin "2") (pinfunction "P$2_2") (pintype "passive"))
    )
    (net (code "54") (name "PWM2H") (class "Default")
      (node (ref "IC_MAIN") (pin "79") (pinfunction "PWM2H/RE3_79") (pintype "bidirectional"))
    )
    (net (code "55") (name "PWM2L") (class "Default")
      (node (ref "F4") (pin "5") (pinfunction "G1_5") (pintype "bidirectional"))
      (node (ref "IC_MAIN") (pin "78") (pinfunction "PWM2L/RE2_78") (pintype "bidirectional"))
      (node (ref "U$58") (pin "2") (pinfunction "P$2_2") (pintype "passive"))
    )
    (net (code "56") (name "PWM3H") (class "Default")
      (node (ref "IC_MAIN") (pin "1") (pinfunction "PWM3H/RE5_1") (pintype "bidirectional"))
    )
    (net (code "57") (name "PWM3L") (class "Default")
      (node (ref "F2") (pin "3") (pinfunction "G2_3") (pintype "bidirectional"))
      (node (ref "IC_MAIN") (pin "80") (pinfunction "PWM3L/RE4_80") (pintype "bidirectional"))
      (node (ref "U$42") (pin "2") (pinfunction "P$2_2") (pintype "passive"))
    )
    (net (code "58") (name "PWM4H") (class "Default")
      (node (ref "IC_MAIN") (pin "3") (pinfunction "PWM4H/RE7_3") (pintype "bidirectional"))
    )
    (net (code "59") (name "PWM4L") (class "Default")
      (node (ref "F2") (pin "5") (pinfunction "G1_5") (pintype "bidirectional"))
      (node (ref "IC_MAIN") (pin "2") (pinfunction "PWM4L/RE6_2") (pintype "bidirectional"))
      (node (ref "U$55") (pin "2") (pinfunction "P$2_2") (pintype "passive"))
    )
    (net (code "60") (name "RA3") (class "Default")
      (node (ref "IC_MAIN") (pin "53") (pinfunction "SDA2/INT4/RA3_53") (pintype "bidirectional"))
      (node (ref "U$64") (pin "1") (pinfunction "1_1") (pintype "bidirectional"))
    )
    (net (code "61") (name "RB2") (class "Default")
      (node (ref "IC_MAIN") (pin "18") (pinfunction "AN2/~{SS1/CN4/RB2}_18") (pintype "bidirectional"))
      (node (ref "U$5") (pin "P$2") (pinfunction "2_P$2") (pintype "bidirectional"))
    )
    (net (code "62") (name "RB3") (class "Default")
      (node (ref "IC_MAIN") (pin "17") (pinfunction "AN3/INDX/CN5/RB3_17") (pintype "bidirectional"))
      (node (ref "U$5") (pin "P$5") (pinfunction "5_P$5") (pintype "bidirectional"))
    )
    (net (code "63") (name "RB4") (class "Default")
      (node (ref "F1") (pin "5") (pinfunction "G1_5") (pintype "bidirectional"))
      (node (ref "IC_MAIN") (pin "16") (pinfunction "AN4/QEA/CN6/RB4_16") (pintype "bidirectional"))
    )
    (net (code "64") (name "RB5") (class "Default")
      (node (ref "F1") (pin "3") (pinfunction "G2_3") (pintype "bidirectional"))
      (node (ref "IC_MAIN") (pin "15") (pinfunction "AN5/QEB/CN7/RB5_15") (pintype "bidirectional"))
    )
    (net (code "65") (name "RB12") (class "Default")
      (node (ref "IC_MAIN") (pin "33") (pinfunction "TCK/AN12/RB12_33") (pintype "bidirectional"))
    )
    (net (code "66") (name "RB13") (class "Default")
      (node (ref "IC_MAIN") (pin "34") (pinfunction "TDI/AN13/RB13_34") (pintype "bidirectional"))
    )
    (net (code "67") (name "RB14") (class "Default")
      (node (ref "IC_MAIN") (pin "35") (pinfunction "~{U2RTS/AN14/RB14}_35") (pintype "bidirectional"))
    )
    (net (code "68") (name "RC13") (class "Default")
      (node (ref "IC_MAIN") (pin "59") (pinfunction "PGD2/EMUD2/SOSCI/CN1/RC13_59") (pintype "bidirectional"))
      (node (ref "U$19") (pin "2") (pinfunction "P$2_2") (pintype "passive"))
    )
    (net (code "69") (name "RC14") (class "Default")
      (node (ref "IC_MAIN") (pin "60") (pinfunction "PGC2/EMUC2/SOSCO/T1CK/CN0/RC14_60") (pintype "bidirectional"))
      (node (ref "U$15") (pin "2") (pinfunction "P$2_2") (pintype "passive"))
    )
    (net (code "70") (name "RD0") (class "Default")
      (node (ref "IC_MAIN") (pin "58") (pinfunction "OC1/RD0_58") (pintype "bidirectional"))
    )
    (net (code "71") (name "RD1") (class "Default")
      (node (ref "IC_MAIN") (pin "61") (pinfunction "OC2/RD1_61") (pintype "bidirectional"))
    )
    (net (code "72") (name "RD2") (class "Default")
      (node (ref "IC_MAIN") (pin "62") (pinfunction "OC3/RD2_62") (pintype "bidirectional"))
    )
    (net (code "73") (name "RD3") (class "Default")
      (node (ref "IC_MAIN") (pin "63") (pinfunction "OC4/RD3_63") (pintype "bidirectional"))
    )
    (net (code "74") (name "RD4") (class "Default")
      (node (ref "IC_MAIN") (pin "66") (pinfunction "OC5/CN13/RD4_66") (pintype "bidirectional"))
      (node (ref "U$67") (pin "P$2") (pinfunction "2_P$2") (pintype "bidirectional"))
    )
    (net (code "75") (name "RD5") (class "Default")
      (node (ref "IC_MAIN") (pin "67") (pinfunction "OC6/CN14/RD5_67") (pintype "bidirectional"))
      (node (ref "U$66") (pin "P$5") (pinfunction "5_P$5") (pintype "bidirectional"))
    )
    (net (code "76") (name "RD6") (class "Default")
      (node (ref "IC_MAIN") (pin "68") (pinfunction "OC7/CN15/RD6_68") (pintype "bidirectional"))
      (node (ref "U$66") (pin "P$2") (pinfunction "2_P$2") (pintype "bidirectional"))
    )
    (net (code "77") (name "RD7") (class "Default")
      (node (ref "IC_MAIN") (pin "69") (pinfunction "OC8/CN16/UPDN/RD7_69") (pintype "bidirectional"))
      (node (ref "U$4") (pin "2") (pinfunction "P$2_2") (pintype "passive"))
      (node (ref "U$64") (pin "2") (pinfunction "2_2") (pintype "bidirectional"))
    )
    (net (code "78") (name "RD9") (class "Default")
      (node (ref "IC_MAIN") (pin "55") (pinfunction "IC2/RD9_55") (pintype "bidirectional"))
    )
    (net (code "79") (name "RD10") (class "Default")
      (node (ref "IC_MAIN") (pin "56") (pinfunction "IC3/RD10_56") (pintype "bidirectional"))
    )
    (net (code "80") (name "RD13") (class "Default")
      (node (ref "IC_MAIN") (pin "65") (pinfunction "IC6/CN19/RD13_65") (pintype "bidirectional"))
      (node (ref "U$67") (pin "P$5") (pinfunction "5_P$5") (pintype "bidirectional"))
    )
    (net (code "81") (name "RD14") (class "Default")
      (node (ref "IC_MAIN") (pin "37") (pinfunction "IC7/~{U1CTS/CN20/RD14}_37") (pintype "bidirectional"))
    )
    (net (code "82") (name "RD15") (class "Default")
      (node (ref "IC_MAIN") (pin "38") (pinfunction "IC8/~{U1RTS/CN21/RD15}_38") (pintype "bidirectional"))
    )
    (net (code "83") (name "RF2") (class "Default")
      (node (ref "F3") (pin "5") (pinfunction "G1_5") (pintype "bidirectional"))
      (node (ref "IC_MAIN") (pin "42") (pinfunction "U1RX/RF2_42") (pintype "bidirectional"))
    )
    (net (code "84") (name "RF3") (class "Default")
      (node (ref "F3") (pin "3") (pinfunction "G2_3") (pintype "bidirectional"))
      (node (ref "IC_MAIN") (pin "41") (pinfunction "U1TX/RF3_41") (pintype "bidirectional"))
    )
    (net (code "85") (name "RF4") (class "Default")
      (node (ref "IC_MAIN") (pin "39") (pinfunction "U2RX/CN17/RF4_39") (pintype "bidirectional"))
      (node (ref "U$20") (pin "P$2") (pinfunction "2_P$2") (pintype "bidirectional"))
    )
    (net (code "86") (name "RF5") (class "Default")
      (node (ref "IC_MAIN") (pin "40") (pinfunction "U2TX/CN18/RF5_40") (pintype "bidirectional"))
      (node (ref "U$20") (pin "P$5") (pinfunction "5_P$5") (pintype "bidirectional"))
    )
    (net (code "87") (name "RG6") (class "Default")
      (node (ref "IC_MAIN") (pin "6") (pinfunction "SCK2/CN8/RG6_6") (pintype "bidirectional"))
      (node (ref "U$64") (pin "4") (pinfunction "4_4") (pintype "bidirectional"))
    )
    (net (code "88") (name "VPP") (class "Default")
      (node (ref "IC_MAIN") (pin "9") (pinfunction "~{MCLR}_9") (pintype "input"))
      (node (ref "U$1") (pin "1") (pinfunction "1_1") (pintype "bidirectional"))
      (node (ref "U$45") (pin "1") (pinfunction "P$1_1") (pintype "passive"))
    )
    (net (code "89") (name "unconnected-(IC_L_I_D-NC1-Pad1)") (class "Default")
      (node (ref "IC_L_I_D") (pin "1") (pinfunction "NC1_1") (pintype "no_connect"))
    )
    (net (code "90") (name "unconnected-(IC_L_I_D-NC4-Pad4)") (class "Default")
      (node (ref "IC_L_I_D") (pin "4") (pinfunction "NC4_4") (pintype "no_connect"))
    )
    (net (code "91") (name "unconnected-(IC_L_I_D-NC7-Pad7)") (class "Default")
      (node (ref "IC_L_I_D") (pin "7") (pinfunction "NC7_7") (pintype "no_connect"))
    )
    (net (code "92") (name "unconnected-(IC_L_I_U-NC1-Pad1)") (class "Default")
      (node (ref "IC_L_I_U") (pin "1") (pinfunction "NC1_1") (pintype "no_connect"))
    )
    (net (code "93") (name "unconnected-(IC_L_I_U-NC4-Pad4)") (class "Default")
      (node (ref "IC_L_I_U") (pin "4") (pinfunction "NC4_4") (pintype "no_connect"))
    )
    (net (code "94") (name "unconnected-(IC_L_I_U-NC7-Pad7)") (class "Default")
      (node (ref "IC_L_I_U") (pin "7") (pinfunction "NC7_7") (pintype "no_connect"))
    )
    (net (code "95") (name "unconnected-(IC_L_O_D-NC1-Pad1)") (class "Default")
      (node (ref "IC_L_O_D") (pin "1") (pinfunction "NC1_1") (pintype "no_connect"))
    )
    (net (code "96") (name "unconnected-(IC_L_O_D-NC4-Pad4)") (class "Default")
      (node (ref "IC_L_O_D") (pin "4") (pinfunction "NC4_4") (pintype "no_connect"))
    )
    (net (code "97") (name "unconnected-(IC_L_O_D-NC7-Pad7)") (class "Default")
      (node (ref "IC_L_O_D") (pin "7") (pinfunction "NC7_7") (pintype "no_connect"))
    )
    (net (code "98") (name "unconnected-(IC_L_O_U-NC1-Pad1)") (class "Default")
      (node (ref "IC_L_O_U") (pin "1") (pinfunction "NC1_1") (pintype "no_connect"))
    )
    (net (code "99") (name "unconnected-(IC_L_O_U-NC4-Pad4)") (class "Default")
      (node (ref "IC_L_O_U") (pin "4") (pinfunction "NC4_4") (pintype "no_connect"))
    )
    (net (code "100") (name "unconnected-(IC_L_O_U-NC7-Pad7)") (class "Default")
      (node (ref "IC_L_O_U") (pin "7") (pinfunction "NC7_7") (pintype "no_connect"))
    )
    (net (code "101") (name "unconnected-(IC_MAIN-AN10{slash}RB10-Pad29)") (class "Default")
      (node (ref "IC_MAIN") (pin "29") (pinfunction "AN10/RB10_29") (pintype "bidirectional"))
    )
    (net (code "102") (name "unconnected-(IC_MAIN-AN11{slash}RB11-Pad30)") (class "Default")
      (node (ref "IC_MAIN") (pin "30") (pinfunction "AN11/RB11_30") (pintype "bidirectional"))
    )
    (net (code "103") (name "unconnected-(IC_MAIN-AN16{slash}T2CK{slash}T7CK{slash}RC1-Pad4)") (class "Default")
      (node (ref "IC_MAIN") (pin "4") (pinfunction "AN16/T2CK/T7CK/RC1_4") (pintype "bidirectional"))
    )
    (net (code "104") (name "unconnected-(IC_MAIN-AN17{slash}T3CK{slash}T6CK{slash}RC2-Pad5)") (class "Default")
      (node (ref "IC_MAIN") (pin "5") (pinfunction "AN17/T3CK/T6CK/RC2_5") (pintype "bidirectional"))
    )
    (net (code "105") (name "unconnected-(IC_MAIN-C1RX{slash}RF0-Pad72)") (class "Default")
      (node (ref "IC_MAIN") (pin "72") (pinfunction "C1RX/RF0_72") (pintype "bidirectional"))
    )
    (net (code "106") (name "unconnected-(IC_MAIN-C1TX{slash}RF1-Pad73)") (class "Default")
      (node (ref "IC_MAIN") (pin "73") (pinfunction "C1TX/RF1_73") (pintype "bidirectional"))
    )
    (net (code "107") (name "unconnected-(IC_MAIN-IC1{slash}RD8-Pad54)") (class "Default")
      (node (ref "IC_MAIN") (pin "54") (pinfunction "IC1/RD8_54") (pintype "bidirectional"))
    )
    (net (code "108") (name "unconnected-(IC_MAIN-IC4{slash}RD11-Pad57)") (class "Default")
      (node (ref "IC_MAIN") (pin "57") (pinfunction "IC4/RD11_57") (pintype "bidirectional"))
    )
    (net (code "109") (name "unconnected-(IC_MAIN-IC5{slash}RD12-Pad64)") (class "Default")
      (node (ref "IC_MAIN") (pin "64") (pinfunction "IC5/RD12_64") (pintype "bidirectional"))
    )
    (net (code "110") (name "unconnected-(IC_MAIN-RG0-Pad75)") (class "Default")
      (node (ref "IC_MAIN") (pin "75") (pinfunction "RG0_75") (pintype "bidirectional"))
    )
    (net (code "111") (name "unconnected-(IC_MAIN-RG1-Pad74)") (class "Default")
      (node (ref "IC_MAIN") (pin "74") (pinfunction "RG1_74") (pintype "bidirectional"))
    )
    (net (code "112") (name "unconnected-(IC_MAIN-SCK1{slash}INT0{slash}RF6-Pad45)") (class "Default")
      (node (ref "IC_MAIN") (pin "45") (pinfunction "SCK1/INT0/RF6_45") (pintype "bidirectional"))
    )
    (net (code "113") (name "unconnected-(IC_MAIN-SCL1{slash}RG2-Pad47)") (class "Default")
      (node (ref "IC_MAIN") (pin "47") (pinfunction "SCL1/RG2_47") (pintype "bidirectional"))
    )
    (net (code "114") (name "unconnected-(IC_MAIN-SCL2{slash}INT3{slash}RA2-Pad52)") (class "Default")
      (node (ref "IC_MAIN") (pin "52") (pinfunction "SCL2/INT3/RA2_52") (pintype "bidirectional"))
    )
    (net (code "115") (name "unconnected-(IC_MAIN-SDA1{slash}RG3-Pad46)") (class "Default")
      (node (ref "IC_MAIN") (pin "46") (pinfunction "SDA1/RG3_46") (pintype "bidirectional"))
    )
    (net (code "116") (name "unconnected-(IC_MAIN-SDI1{slash}RF7-Pad44)") (class "Default")
      (node (ref "IC_MAIN") (pin "44") (pinfunction "SDI1/RF7_44") (pintype "bidirectional"))
    )
    (net (code "117") (name "unconnected-(IC_MAIN-SDI2{slash}CN9{slash}RG7-Pad7)") (class "Default")
      (node (ref "IC_MAIN") (pin "7") (pinfunction "SDI2/CN9/RG7_7") (pintype "bidirectional"))
    )
    (net (code "118") (name "unconnected-(IC_MAIN-SDO1{slash}RF8-Pad43)") (class "Default")
      (node (ref "IC_MAIN") (pin "43") (pinfunction "SDO1/RF8_43") (pintype "bidirectional"))
    )
    (net (code "119") (name "unconnected-(IC_MAIN-SDO2{slash}CN10{slash}RG8-Pad8)") (class "Default")
      (node (ref "IC_MAIN") (pin "8") (pinfunction "SDO2/CN10/RG8_8") (pintype "bidirectional"))
    )
    (net (code "120") (name "unconnected-(IC_MAIN-TDO{slash}~{FLTB{slash}INT2{slash}RE9}-Pad14)") (class "Default")
      (node (ref "IC_MAIN") (pin "14") (pinfunction "TDO/~{FLTB/INT2/RE9}_14") (pintype "bidirectional"))
    )
    (net (code "121") (name "unconnected-(IC_MAIN-TMS{slash}~{FLTA{slash}INT1{slash}RE8}-Pad13)") (class "Default")
      (node (ref "IC_MAIN") (pin "13") (pinfunction "TMS/~{FLTA/INT1/RE8}_13") (pintype "bidirectional"))
    )
    (net (code "122") (name "unconnected-(IC_MAIN-VREF+{slash}RA10-Pad24)") (class "Default")
      (node (ref "IC_MAIN") (pin "24") (pinfunction "VREF+/RA10_24") (pintype "bidirectional"))
    )
    (net (code "123") (name "unconnected-(IC_MAIN-VREF-{slash}RA9-Pad23)") (class "Default")
      (node (ref "IC_MAIN") (pin "23") (pinfunction "VREF-/RA9_23") (pintype "bidirectional"))
    )
    (net (code "124") (name "unconnected-(IC_MAIN-~{SS2{slash}CN11{slash}RG9}-Pad10)") (class "Default")
      (node (ref "IC_MAIN") (pin "10") (pinfunction "~{SS2/CN11/RG9}_10") (pintype "bidirectional"))
    )
    (net (code "125") (name "unconnected-(IC_MAIN-~{U2CTS{slash}AN8{slash}RB8}-Pad27)") (class "Default")
      (node (ref "IC_MAIN") (pin "27") (pinfunction "~{U2CTS/AN8/RB8}_27") (pintype "bidirectional"))
    )
    (net (code "126") (name "unconnected-(IC_R_I_D-NC1-Pad1)") (class "Default")
      (node (ref "IC_R_I_D") (pin "1") (pinfunction "NC1_1") (pintype "no_connect"))
    )
    (net (code "127") (name "unconnected-(IC_R_I_D-NC4-Pad4)") (class "Default")
      (node (ref "IC_R_I_D") (pin "4") (pinfunction "NC4_4") (pintype "no_connect"))
    )
    (net (code "128") (name "unconnected-(IC_R_I_D-NC7-Pad7)") (class "Default")
      (node (ref "IC_R_I_D") (pin "7") (pinfunction "NC7_7") (pintype "no_connect"))
    )
    (net (code "129") (name "unconnected-(IC_R_I_U-NC1-Pad1)") (class "Default")
      (node (ref "IC_R_I_U") (pin "1") (pinfunction "NC1_1") (pintype "no_connect"))
    )
    (net (code "130") (name "unconnected-(IC_R_I_U-NC4-Pad4)") (class "Default")
      (node (ref "IC_R_I_U") (pin "4") (pinfunction "NC4_4") (pintype "no_connect"))
    )
    (net (code "131") (name "unconnected-(IC_R_I_U-NC7-Pad7)") (class "Default")
      (node (ref "IC_R_I_U") (pin "7") (pinfunction "NC7_7") (pintype "no_connect"))
    )
    (net (code "132") (name "unconnected-(IC_R_O_D-NC1-Pad1)") (class "Default")
      (node (ref "IC_R_O_D") (pin "1") (pinfunction "NC1_1") (pintype "no_connect"))
    )
    (net (code "133") (name "unconnected-(IC_R_O_D-NC4-Pad4)") (class "Default")
      (node (ref "IC_R_O_D") (pin "4") (pinfunction "NC4_4") (pintype "no_connect"))
    )
    (net (code "134") (name "unconnected-(IC_R_O_D-NC7-Pad7)") (class "Default")
      (node (ref "IC_R_O_D") (pin "7") (pinfunction "NC7_7") (pintype "no_connect"))
    )
    (net (code "135") (name "unconnected-(IC_R_O_U-NC1-Pad1)") (class "Default")
      (node (ref "IC_R_O_U") (pin "1") (pinfunction "NC1_1") (pintype "no_connect"))
    )
    (net (code "136") (name "unconnected-(IC_R_O_U-NC4-Pad4)") (class "Default")
      (node (ref "IC_R_O_U") (pin "4") (pinfunction "NC4_4") (pintype "no_connect"))
    )
    (net (code "137") (name "unconnected-(IC_R_O_U-NC7-Pad7)") (class "Default")
      (node (ref "IC_R_O_U") (pin "7") (pinfunction "NC7_7") (pintype "no_connect"))
    )
    (net (code "138") (name "unconnected-(U$64-Pad5)") (class "Default")
      (node (ref "U$64") (pin "5") (pinfunction "5_5") (pintype "bidirectional"))
    )
  )
)
